# main_schematic.net
KiCad netlist of a schematic drawn in Altium Designer
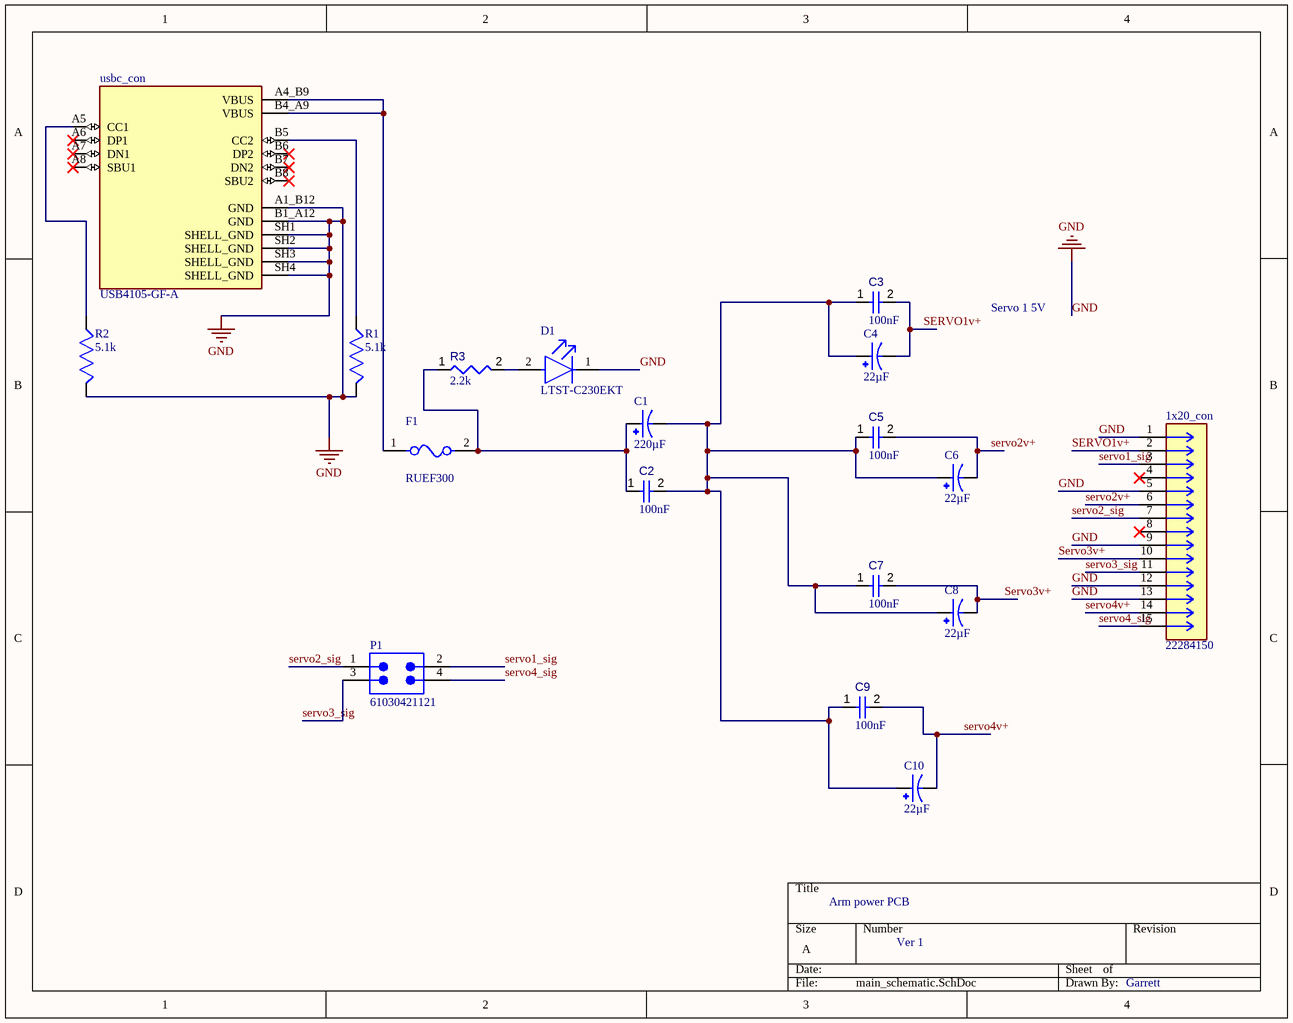
[diagram p0: main_schematic.SchDoc]

(export (version "E")
  (design (tool "Eeschema 10.0.6"))
  (components
    (comp (ref "1x20_con")
      (value "22284150")
      (footprint "CONN_SD-42375-001_M240_15_MOL")
      (fields (field (name "MF") "Molex"))
      (libsource (lib "Garrett Vieira") (part "22284150"))
    )
    (comp (ref "C1")
      (value "220µF")
      (footprint "CAP_EEEHD1A221AP")
      (description "Tá»¥ Ä‘iá»‡n phÃ¢n nhÃ´m 220ÂµF 10V hÆ°á»›ng tÃ¢m, cÃ³ thá»ƒ - SMD 5000 giá» á»Ÿ 105Â°C")
      (fields (field (name "MP") "EEEHD1A221AP") (field (name "MF") "Panasonic"))
      (libsource (lib "Garrett Vieira") (part "EEEHD1A221AP"))
    )
    (comp (ref "C2")
      (value "100nF")
      (footprint "CAPC0402(1005)60_L")
      (description "Chip Capacitor, 100nF +/-20%, 50V, 0402, Thickness 0.6 mm")
      (fields (field (name "TOLERANCE") "10%") (field (name "Comment") "Capacitor 100nF +/-20% 50V 0402"))
      (libsource (lib "Garrett Vieira") (part "CAP-NP-2"))
    )
    (comp (ref "C3")
      (value "100nF")
      (footprint "CAPC0402(1005)60_L")
      (description "Chip Capacitor, 100nF +/-20%, 50V, 0402, Thickness 0.6 mm")
      (fields (field (name "TOLERANCE") "10%") (field (name "Comment") "Capacitor 100nF +/-20% 50V 0402"))
      (libsource (lib "Garrett Vieira") (part "CAP-NP-2"))
    )
    (comp (ref "C4")
      (value "22µF")
      (footprint "CAPPRD200W45D500H500")
      (description "Capacitor; Aluminum Electrolytic; Cap 22uF; Vol-Rtg 16V; Radial; Ks; Height 5mm")
      (fields (field (name "MF") "Panasonic") (field (name "MP") "ECE-A1CKS220"))
      (libsource (lib "Garrett Vieira") (part "ECEA1CKS220"))
    )
    (comp (ref "C5")
      (value "100nF")
      (footprint "CAPC0402(1005)60_L")
      (description "Chip Capacitor, 100nF +/-20%, 50V, 0402, Thickness 0.6 mm")
      (fields (field (name "TOLERANCE") "10%") (field (name "Comment") "Capacitor 100nF +/-20% 50V 0402"))
      (libsource (lib "Garrett Vieira") (part "CAP-NP-2"))
    )
    (comp (ref "C6")
      (value "22µF")
      (footprint "CAPPRD200W45D500H500")
      (description "Capacitor; Aluminum Electrolytic; Cap 22uF; Vol-Rtg 16V; Radial; Ks; Height 5mm")
      (fields (field (name "MF") "Panasonic") (field (name "MP") "ECE-A1CKS220"))
      (libsource (lib "Garrett Vieira") (part "ECEA1CKS220"))
    )
    (comp (ref "C7")
      (value "100nF")
      (footprint "CAPC0402(1005)60_L")
      (description "Chip Capacitor, 100nF +/-20%, 50V, 0402, Thickness 0.6 mm")
      (fields (field (name "TOLERANCE") "10%") (field (name "Comment") "Capacitor 100nF +/-20% 50V 0402"))
      (libsource (lib "Garrett Vieira") (part "CAP-NP-2"))
    )
    (comp (ref "C8")
      (value "22µF")
      (footprint "CAPPRD200W45D500H500")
      (description "Capacitor; Aluminum Electrolytic; Cap 22uF; Vol-Rtg 16V; Radial; Ks; Height 5mm")
      (fields (field (name "MF") "Panasonic") (field (name "MP") "ECE-A1CKS220"))
      (libsource (lib "Garrett Vieira") (part "ECEA1CKS220"))
    )
    (comp (ref "C9")
      (value "100nF")
      (footprint "CAPC0402(1005)60_L")
      (description "Chip Capacitor, 100nF +/-20%, 50V, 0402, Thickness 0.6 mm")
      (fields (field (name "TOLERANCE") "10%") (field (name "Comment") "Capacitor 100nF +/-20% 50V 0402"))
      (libsource (lib "Garrett Vieira") (part "CAP-NP-2"))
    )
    (comp (ref "C10")
      (value "22µF")
      (footprint "CAPPRD200W45D500H500")
      (description "Capacitor; Aluminum Electrolytic; Cap 22uF; Vol-Rtg 16V; Radial; Ks; Height 5mm")
      (fields (field (name "MF") "Panasonic") (field (name "MP") "ECE-A1CKS220"))
      (libsource (lib "Garrett Vieira") (part "ECEA1CKS220"))
    )
    (comp (ref "D1")
      (value "LTST-C230EKT")
      (footprint "FP-LTST-C230EKT-MFG")
      (description "LED RED CLEAR CHIP SMD")
      (libsource (lib "Altium Content Vault") (part "8706943c75ba83719d021d2fdc84c58"))
    )
    (comp (ref "F1")
      (value "RUEF300")
      (footprint "FP-RUEF300-MFG")
      (description "PTC RESET FUSE 30V 3A RADIAL")
      (fields
        (field (name "OCTOPART") "https://octopart.com/ruef300-littelfuse-74215783")
        (field (name "MANUFACTURER") "Littelfuse")
      )
      (libsource (lib "Altium Content Vault") (part "5bcf9b9f640e542cf0359d10258e979"))
    )
    (comp (ref "P1")
      (value "61030421121")
      (footprint "61030421121")
      (description "SMT Vertical Pin Header WR-PHD, Pitch 2.54 mm, Dual Row, 4 pins")
      (libsource (lib "Altium Content Vault") (part "Header_Male_2R_04P"))
    )
    (comp (ref "R1")
      (value "5.1k")
      (footprint "RESC1005X40")
      (description "Res Thick Film 0402 5.1K Ohm 1% 1/16W Â±100ppm/Â°C Molded SMD SMD Paper T/R")
      (fields (field (name "MF") "Yageo") (field (name "MP") "RC0402FR-135K1L"))
      (libsource (lib "Garrett Vieira") (part "RC0402FR-135K1L"))
    )
    (comp (ref "R2")
      (value "5.1k")
      (footprint "RESC1005X40")
      (description "Res Thick Film 0402 5.1K Ohm 1% 1/16W Â±100ppm/Â°C Molded SMD SMD Paper T/R")
      (fields (field (name "MF") "Yageo") (field (name "MP") "RC0402FR-135K1L"))
      (libsource (lib "Garrett Vieira") (part "RC0402FR-135K1L"))
    )
    (comp (ref "R3")
      (value "2.2k")
      (footprint "RESC0402(1005)_L")
      (description "2K2 0.063W 5% 0402 (1005 Metric)  SMD")
      (fields (field (name "TOLERANCE") "5%") (field (name "POWER") "63mW"))
      (libsource (lib "Garrett Vieira") (part "2D2KR2J"))
    )
    (comp (ref "usbc_con")
      (value "USB4105-GF-A")
      (footprint "GCT_USB4105-GF-A")
      (fields (field (name "MF") "{'manufacturer': u'GCT'}"))
      (libsource (lib "Garrett Vieira") (part "USB4105-GF-A"))
    )
  )
  (nets
    (net (code "1") (name "/SERVO1v+") (class "Default")
      (node (ref "1x20_con") (pin "2") (pinfunction "2_2") (pintype "passive"))
      (node (ref "C3") (pin "2") (pinfunction "2_2") (pintype "passive"))
      (node (ref "C4") (pin "N") (pinfunction "N_N") (pintype "passive"))
    )
    (net (code "2") (name "/Servo3v+") (class "Default")
      (node (ref "1x20_con") (pin "10") (pinfunction "10_10") (pintype "passive"))
      (node (ref "C7") (pin "2") (pinfunction "2_2") (pintype "passive"))
      (node (ref "C8") (pin "N") (pinfunction "N_N") (pintype "passive"))
    )
    (net (code "3") (name "/servo1_sig") (class "Default")
      (node (ref "1x20_con") (pin "3") (pinfunction "3_3") (pintype "passive"))
      (node (ref "P1") (pin "2") (pinfunction "2_2") (pintype "passive"))
    )
    (net (code "4") (name "/servo2_sig") (class "Default")
      (node (ref "1x20_con") (pin "7") (pinfunction "7_7") (pintype "passive"))
      (node (ref "P1") (pin "1") (pinfunction "1_1") (pintype "passive"))
    )
    (net (code "5") (name "/servo2v+") (class "Default")
      (node (ref "1x20_con") (pin "6") (pinfunction "6_6") (pintype "passive"))
      (node (ref "C5") (pin "2") (pinfunction "2_2") (pintype "passive"))
      (node (ref "C6") (pin "N") (pinfunction "N_N") (pintype "passive"))
    )
    (net (code "6") (name "/servo3_sig") (class "Default")
      (node (ref "1x20_con") (pin "11") (pinfunction "11_11") (pintype "passive"))
      (node (ref "P1") (pin "3") (pinfunction "3_3") (pintype "passive"))
    )
    (net (code "7") (name "/servo4_sig") (class "Default")
      (node (ref "1x20_con") (pin "15") (pinfunction "15_15") (pintype "passive"))
      (node (ref "P1") (pin "4") (pinfunction "4_4") (pintype "passive"))
    )
    (net (code "8") (name "/servo4v+") (class "Default")
      (node (ref "1x20_con") (pin "14") (pinfunction "14_14") (pintype "passive"))
      (node (ref "C10") (pin "N") (pinfunction "N_N") (pintype "passive"))
      (node (ref "C9") (pin "2") (pinfunction "2_2") (pintype "passive"))
    )
    (net (code "9") (name "GND") (class "Default")
      (node (ref "1x20_con") (pin "1") (pinfunction "1_1") (pintype "passive"))
      (node (ref "1x20_con") (pin "12") (pinfunction "12_12") (pintype "passive"))
      (node (ref "1x20_con") (pin "13") (pinfunction "13_13") (pintype "passive"))
      (node (ref "1x20_con") (pin "5") (pinfunction "5_5") (pintype "passive"))
      (node (ref "1x20_con") (pin "9") (pinfunction "9_9") (pintype "passive"))
      (node (ref "D1") (pin "1") (pinfunction "C_1") (pintype "passive"))
      (node (ref "R1") (pin "1") (pinfunction "1_1") (pintype "passive"))
      (node (ref "R2") (pin "1") (pinfunction "1_1") (pintype "passive"))
      (node (ref "usbc_con") (pin "A1_B12") (pinfunction "GND_A1_B12") (pintype "power_in"))
      (node (ref "usbc_con") (pin "B1_A12") (pinfunction "GND_B1_A12") (pintype "power_in"))
      (node (ref "usbc_con") (pin "SH1") (pinfunction "SHELL_GND_SH1") (pintype "power_in"))
      (node (ref "usbc_con") (pin "SH2") (pinfunction "SHELL_GND_SH2") (pintype "power_in"))
      (node (ref "usbc_con") (pin "SH3") (pinfunction "SHELL_GND_SH3") (pintype "power_in"))
      (node (ref "usbc_con") (pin "SH4") (pinfunction "SHELL_GND_SH4") (pintype "power_in"))
    )
    (net (code "10") (name "Net-(C1-Pad1)") (class "Default")
      (node (ref "C1") (pin "1") (pinfunction "1_1") (pintype "passive"))
      (node (ref "C2") (pin "1") (pinfunction "1_1") (pintype "passive"))
      (node (ref "F1") (pin "2") (pinfunction "2_2") (pintype "passive"))
      (node (ref "R3") (pin "1") (pinfunction "1_1") (pintype "passive"))
    )
    (net (code "11") (name "Net-(C1-Pad2)") (class "Default")
      (node (ref "C1") (pin "2") (pinfunction "2_2") (pintype "passive"))
      (node (ref "C10") (pin "P") (pinfunction "P_P") (pintype "passive"))
      (node (ref "C2") (pin "2") (pinfunction "2_2") (pintype "passive"))
      (node (ref "C3") (pin "1") (pinfunction "1_1") (pintype "passive"))
      (node (ref "C4") (pin "P") (pinfunction "P_P") (pintype "passive"))
      (node (ref "C5") (pin "1") (pinfunction "1_1") (pintype "passive"))
      (node (ref "C6") (pin "P") (pinfunction "P_P") (pintype "passive"))
      (node (ref "C7") (pin "1") (pinfunction "1_1") (pintype "passive"))
      (node (ref "C8") (pin "P") (pinfunction "P_P") (pintype "passive"))
      (node (ref "C9") (pin "1") (pinfunction "1_1") (pintype "passive"))
    )
    (net (code "12") (name "Net-(D1-A)") (class "Default")
      (node (ref "D1") (pin "2") (pinfunction "A_2") (pintype "passive"))
      (node (ref "R3") (pin "2") (pinfunction "2_2") (pintype "passive"))
    )
    (net (code "13") (name "Net-(F1-Pad1)") (class "Default")
      (node (ref "F1") (pin "1") (pinfunction "1_1") (pintype "passive"))
      (node (ref "usbc_con") (pin "A4_B9") (pinfunction "VBUS_A4_B9") (pintype "power_in"))
      (node (ref "usbc_con") (pin "B4_A9") (pinfunction "VBUS_B4_A9") (pintype "power_in"))
    )
    (net (code "14") (name "Net-(usbc_con-CC1)") (class "Default")
      (node (ref "R2") (pin "2") (pinfunction "2_2") (pintype "passive"))
      (node (ref "usbc_con") (pin "A5") (pinfunction "CC1_A5") (pintype "bidirectional"))
    )
    (net (code "15") (name "Net-(usbc_con-CC2)") (class "Default")
      (node (ref "R1") (pin "2") (pinfunction "2_2") (pintype "passive"))
      (node (ref "usbc_con") (pin "B5") (pinfunction "CC2_B5") (pintype "bidirectional"))
    )
    (net (code "16") (name "unconnected-(1x20_con-Pad4)") (class "Default")
      (node (ref "1x20_con") (pin "4") (pinfunction "4_4") (pintype "passive+no_connect"))
    )
    (net (code "17") (name "unconnected-(1x20_con-Pad8)") (class "Default")
      (node (ref "1x20_con") (pin "8") (pinfunction "8_8") (pintype "passive+no_connect"))
    )
    (net (code "18") (name "unconnected-(usbc_con-DN1-PadA7)") (class "Default")
      (node (ref "usbc_con") (pin "A7") (pinfunction "DN1_A7") (pintype "bidirectional+no_connect"))
    )
    (net (code "19") (name "unconnected-(usbc_con-DN2-PadB7)") (class "Default")
      (node (ref "usbc_con") (pin "B7") (pinfunction "DN2_B7") (pintype "bidirectional+no_connect"))
    )
    (net (code "20") (name "unconnected-(usbc_con-DP1-PadA6)") (class "Default")
      (node (ref "usbc_con") (pin "A6") (pinfunction "DP1_A6") (pintype "bidirectional+no_connect"))
    )
    (net (code "21") (name "unconnected-(usbc_con-DP2-PadB6)") (class "Default")
      (node (ref "usbc_con") (pin "B6") (pinfunction "DP2_B6") (pintype "bidirectional+no_connect"))
    )
    (net (code "22") (name "unconnected-(usbc_con-SBU1-PadA8)") (class "Default")
      (node (ref "usbc_con") (pin "A8") (pinfunction "SBU1_A8") (pintype "bidirectional+no_connect"))
    )
    (net (code "23") (name "unconnected-(usbc_con-SBU2-PadB8)") (class "Default")
      (node (ref "usbc_con") (pin "B8") (pinfunction "SBU2_B8") (pintype "bidirectional+no_connect"))
    )
  )
)
